# Akpinar_Lixie_Versorgung.net
KiCad netlist of a schematic drawn in EAGLE
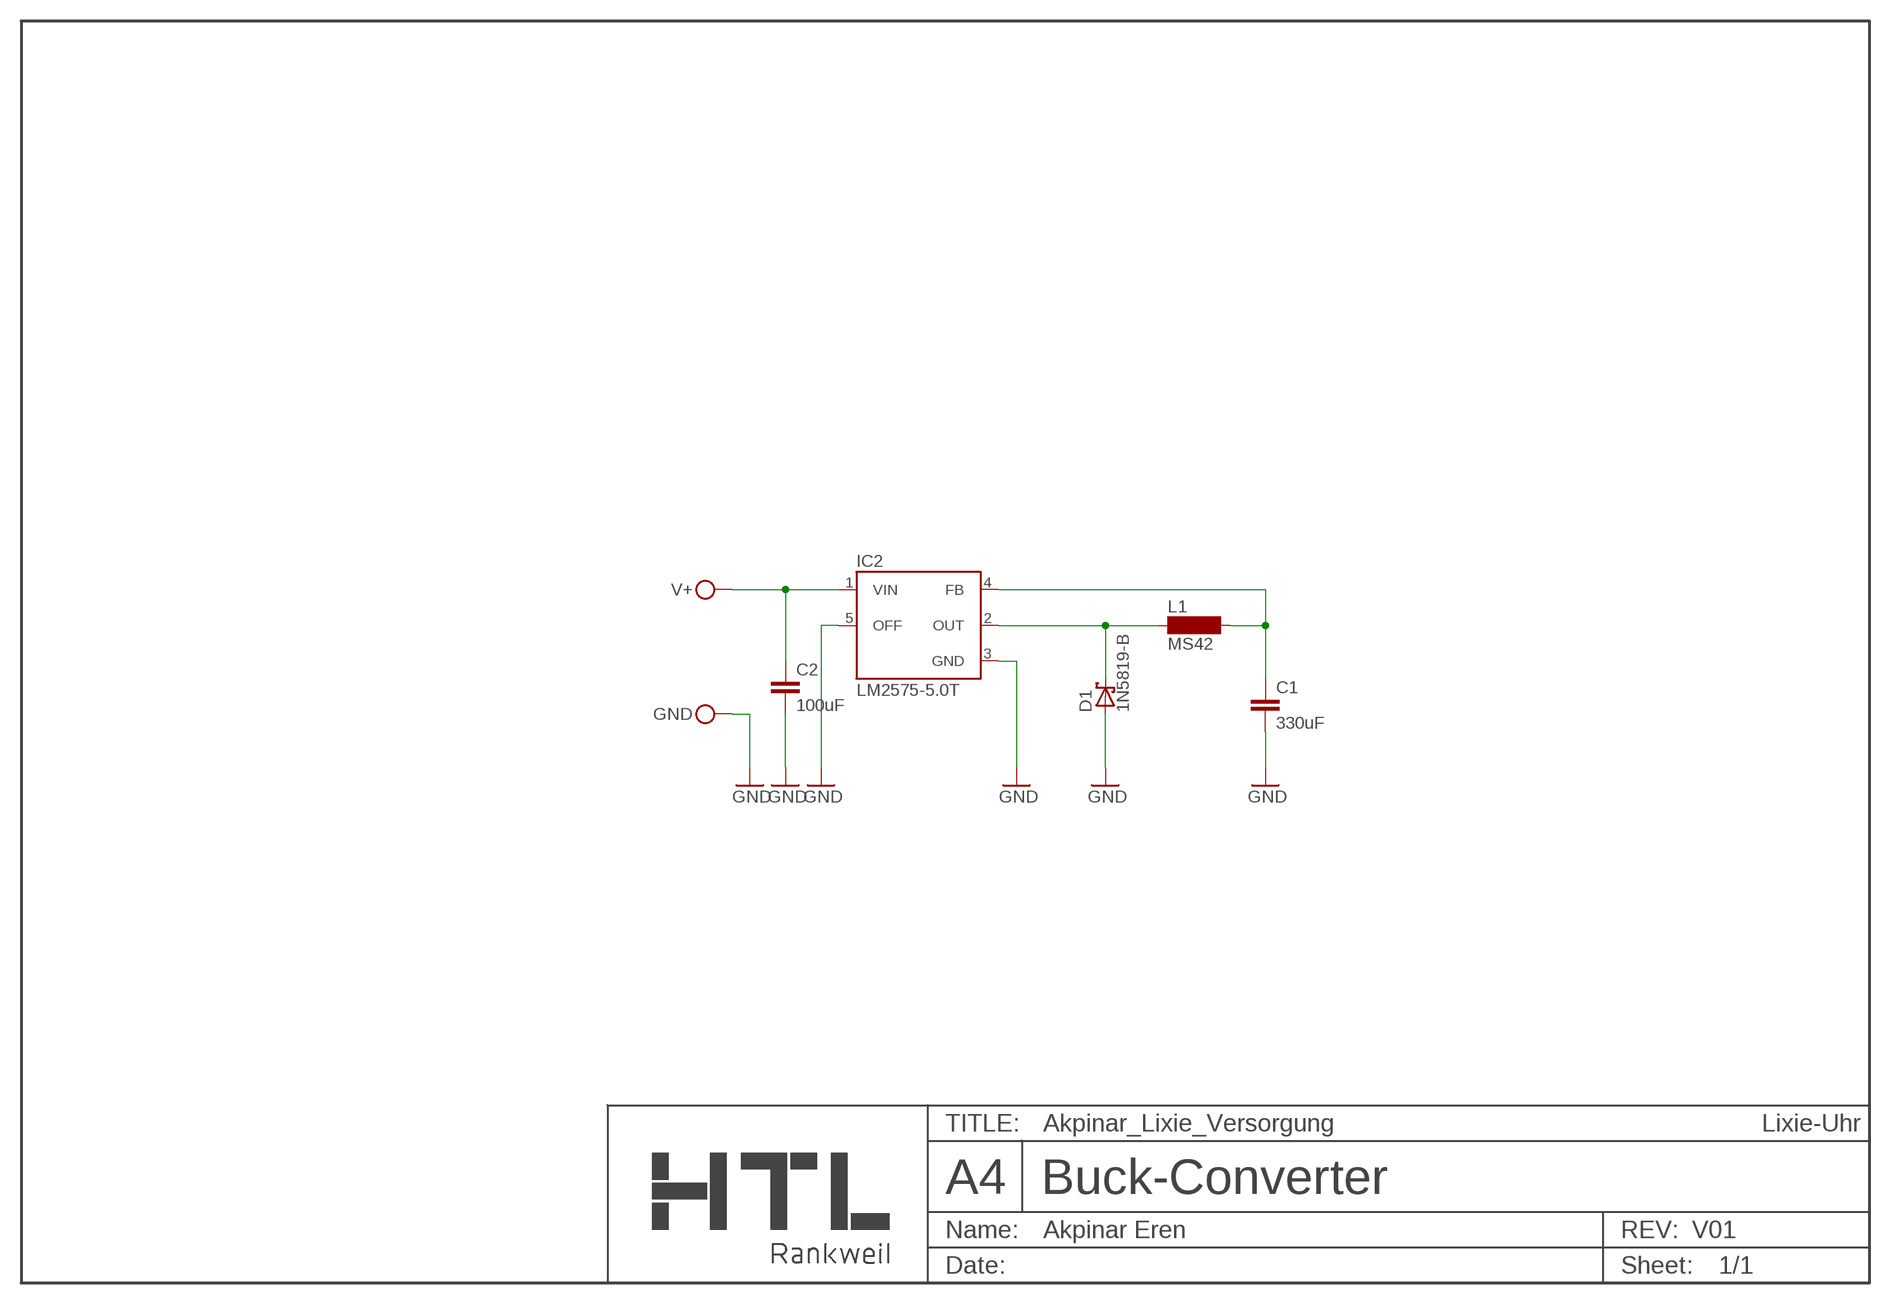
[diagram p0: schematic, sheet 1]

(export (version "E")
  (design (tool "Eeschema 10.0.6"))
  (components
    (comp (ref "C1")
      (value "330uF")
      (footprint "eagle-import:C1206")
      (libsource (lib "eagle-import") (part "C-1206"))
    )
    (comp (ref "C2")
      (value "100uF")
      (footprint "eagle-import:C1206")
      (libsource (lib "eagle-import") (part "C-1206"))
    )
    (comp (ref "D1")
      (value "1N5819-B")
      (footprint "eagle-import:DO41-7.6")
      (libsource (lib "eagle-import") (part "1N5819-B"))
    )
    (comp (ref "FRAME1")
      (value "HTL-A4-HA4H")
      (footprint "eagle-import:HTL-A4-H")
      (libsource (lib "eagle-import") (part "HTL-A4-HA4H"))
    )
    (comp (ref "GND")
      (value "LPIN")
      (footprint "eagle-import:LPIN")
      (libsource (lib "eagle-import") (part "LPIN"))
    )
    (comp (ref "IC2")
      (value "LM2575-5.0T")
      (footprint "eagle-import:TO220-5")
      (libsource (lib "eagle-import") (part "LM2575-5.0T"))
    )
    (comp (ref "L1")
      (value "MS42")
      (footprint "eagle-import:MS42")
      (libsource (lib "eagle-import") (part "MS42"))
    )
    (comp (ref "V+")
      (value "LPIN")
      (footprint "eagle-import:LPIN")
      (libsource (lib "eagle-import") (part "LPIN"))
    )
  )
  (nets
    (net (code "1") (name "GND") (class "Default")
      (node (ref "C1") (pin "2") (pinfunction "2_2") (pintype "passive"))
      (node (ref "C2") (pin "2") (pinfunction "2_2") (pintype "passive"))
      (node (ref "D1") (pin "A") (pinfunction "A_A") (pintype "passive"))
      (node (ref "GND") (pin "P$1") (pinfunction "KL_P$1") (pintype "passive"))
      (node (ref "IC2") (pin "3") (pinfunction "GND_3") (pintype "power_in"))
      (node (ref "IC2") (pin "5") (pinfunction "OFF_5") (pintype "input"))
    )
    (net (code "2") (name "Net-(IC2-FB)") (class "Default")
      (node (ref "C1") (pin "1") (pinfunction "1_1") (pintype "passive"))
      (node (ref "IC2") (pin "4") (pinfunction "FB_4") (pintype "input"))
      (node (ref "L1") (pin "2") (pinfunction "2_2") (pintype "passive"))
    )
    (net (code "3") (name "Net-(IC2-OUT)") (class "Default")
      (node (ref "D1") (pin "C") (pinfunction "C_C") (pintype "passive"))
      (node (ref "IC2") (pin "2") (pinfunction "OUT_2") (pintype "output"))
      (node (ref "L1") (pin "1") (pinfunction "1_1") (pintype "passive"))
    )
    (net (code "4") (name "Net-(IC2-VIN)") (class "Default")
      (node (ref "C2") (pin "1") (pinfunction "1_1") (pintype "passive"))
      (node (ref "IC2") (pin "1") (pinfunction "VIN_1") (pintype "power_in"))
      (node (ref "V+") (pin "P$1") (pinfunction "KL_P$1") (pintype "passive"))
    )
  )
)
